# LowSide_Analog_protections.net
KiCad netlist of a schematic drawn in Altium Designer
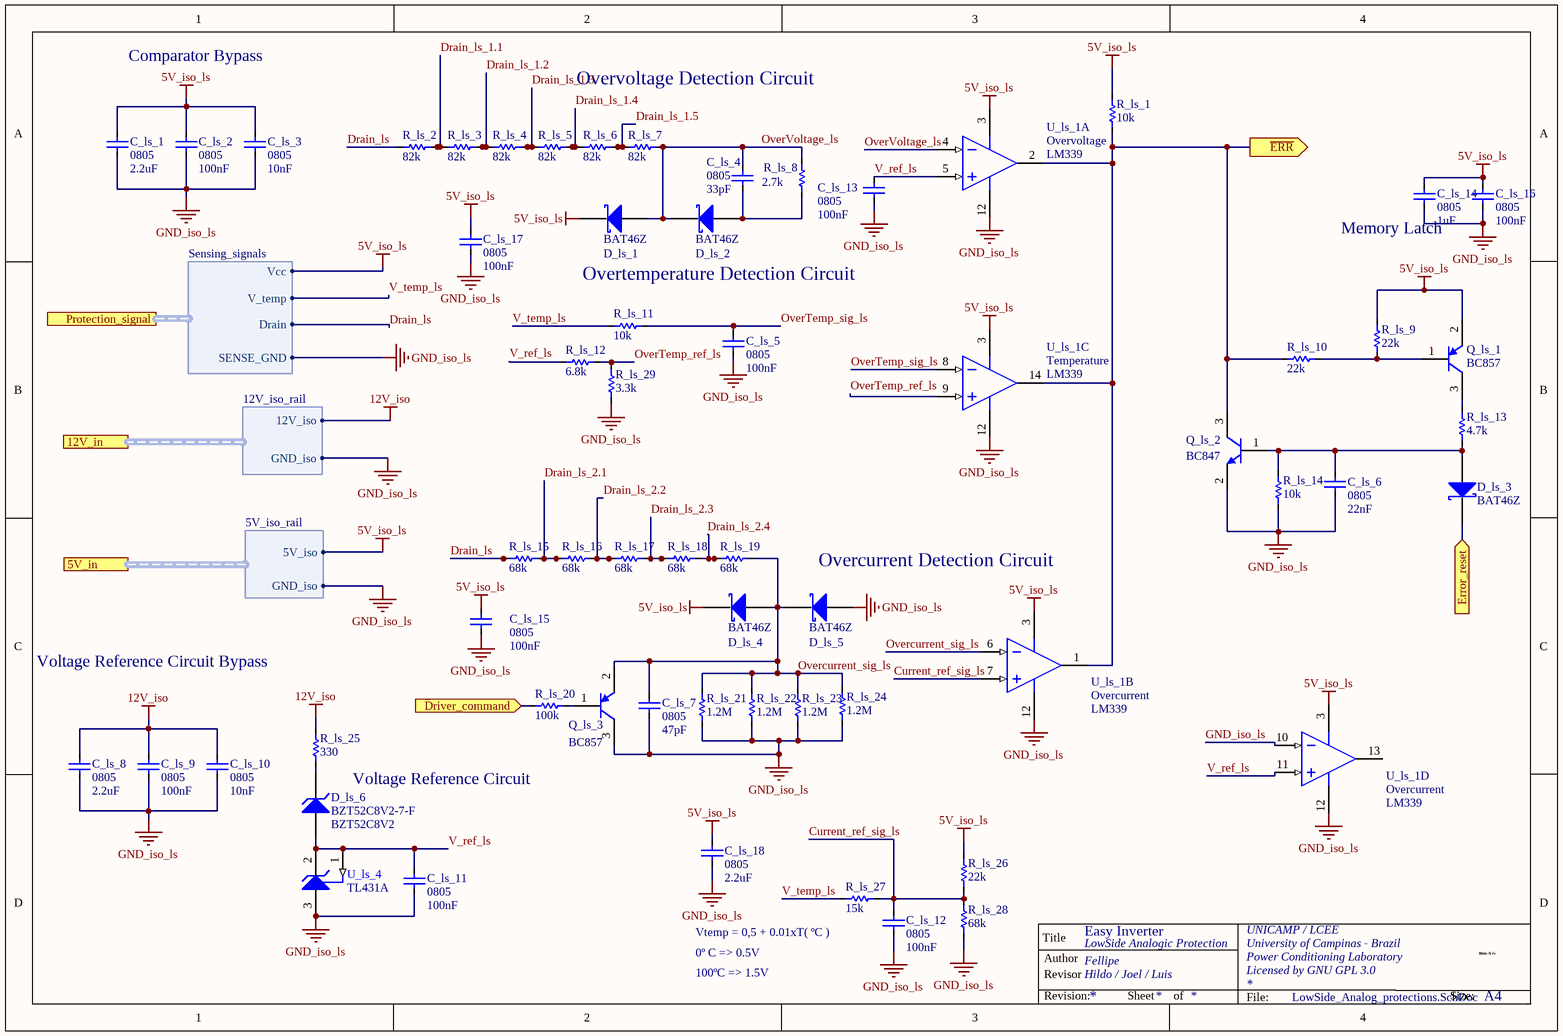
[diagram p0: LowSide_Analog_protections.SchDoc]

(export (version "E")
  (design (tool "Eeschema 10.0.6"))
  (components
    (comp (ref "C_ls_1")
      (value "0805")
      (footprint "Capacitor 0805")
      (description "SMD ceramic capacitor 0805")
      (fields (field (name "ALTIUM_VALUE") "2.2uF"))
      (libsource (lib "EdgeInverter_library") (part "Capacitor 0805"))
    )
    (comp (ref "C_ls_2")
      (value "0805")
      (footprint "Capacitor 0805")
      (description "SMD ceramic capacitor 0805")
      (fields (field (name "ALTIUM_VALUE") "100nF"))
      (libsource (lib "EdgeInverter_library") (part "Capacitor 0805"))
    )
    (comp (ref "C_ls_3")
      (value "0805")
      (footprint "Capacitor 0805")
      (description "SMD ceramic capacitor 0805")
      (fields (field (name "ALTIUM_VALUE") "10nF"))
      (libsource (lib "EdgeInverter_library") (part "Capacitor 0805"))
    )
    (comp (ref "C_ls_4")
      (value "0805")
      (footprint "Capacitor 0805")
      (description "SMD ceramic capacitor 0805")
      (fields (field (name "ALTIUM_VALUE") "33pF"))
      (libsource (lib "EdgeInverter_library") (part "Capacitor 0805"))
    )
    (comp (ref "C_ls_5")
      (value "0805")
      (footprint "Capacitor 0805")
      (description "SMD ceramic capacitor 0805")
      (fields (field (name "ALTIUM_VALUE") "100nF"))
      (libsource (lib "EdgeInverter_library") (part "Capacitor 0805"))
    )
    (comp (ref "C_ls_6")
      (value "0805")
      (footprint "Capacitor 0805")
      (description "SMD ceramic capacitor 0805")
      (fields (field (name "ALTIUM_VALUE") "22nF"))
      (libsource (lib "EdgeInverter_library") (part "Capacitor 0805"))
    )
    (comp (ref "C_ls_7")
      (value "0805")
      (footprint "Capacitor 0805")
      (description "SMD ceramic capacitor 0805")
      (fields (field (name "ALTIUM_VALUE") "47pF"))
      (libsource (lib "EdgeInverter_library") (part "Capacitor 0805"))
    )
    (comp (ref "C_ls_8")
      (value "0805")
      (footprint "Capacitor 0805")
      (description "SMD ceramic capacitor 0805")
      (fields (field (name "ALTIUM_VALUE") "2.2uF"))
      (libsource (lib "EdgeInverter_library") (part "Capacitor 0805"))
    )
    (comp (ref "C_ls_9")
      (value "0805")
      (footprint "Capacitor 0805")
      (description "SMD ceramic capacitor 0805")
      (fields (field (name "ALTIUM_VALUE") "100nF"))
      (libsource (lib "EdgeInverter_library") (part "Capacitor 0805"))
    )
    (comp (ref "C_ls_10")
      (value "0805")
      (footprint "Capacitor 0805")
      (description "SMD ceramic capacitor 0805")
      (fields (field (name "ALTIUM_VALUE") "10nF"))
      (libsource (lib "EdgeInverter_library") (part "Capacitor 0805"))
    )
    (comp (ref "C_ls_11")
      (value "0805")
      (footprint "Capacitor 0805")
      (description "SMD ceramic capacitor 0805")
      (fields (field (name "ALTIUM_VALUE") "100nF"))
      (libsource (lib "EdgeInverter_library") (part "Capacitor 0805"))
    )
    (comp (ref "C_ls_12")
      (value "0805")
      (footprint "Capacitor 0805")
      (description "SMD ceramic capacitor 0805")
      (fields (field (name "ALTIUM_VALUE") "100nF"))
      (libsource (lib "EdgeInverter_library") (part "Capacitor 0805"))
    )
    (comp (ref "C_ls_13")
      (value "0805")
      (footprint "Capacitor 0805")
      (description "SMD ceramic capacitor 0805")
      (fields (field (name "ALTIUM_VALUE") "100nF"))
      (libsource (lib "EdgeInverter_library") (part "Capacitor 0805"))
    )
    (comp (ref "C_ls_14")
      (value "0805")
      (footprint "Capacitor 0805")
      (description "SMD ceramic capacitor 0805")
      (fields (field (name "ALTIUM_VALUE") "1uF"))
      (libsource (lib "EdgeInverter_library") (part "Capacitor 0805"))
    )
    (comp (ref "C_ls_15")
      (value "0805")
      (footprint "Capacitor 0805")
      (description "SMD ceramic capacitor 0805")
      (fields (field (name "ALTIUM_VALUE") "100nF"))
      (libsource (lib "EdgeInverter_library") (part "Capacitor 0805"))
    )
    (comp (ref "C_ls_16")
      (value "0805")
      (footprint "Capacitor 0805")
      (description "SMD ceramic capacitor 0805")
      (fields (field (name "ALTIUM_VALUE") "100nF"))
      (libsource (lib "EdgeInverter_library") (part "Capacitor 0805"))
    )
    (comp (ref "C_ls_17")
      (value "0805")
      (footprint "Capacitor 0805")
      (description "SMD ceramic capacitor 0805")
      (fields (field (name "ALTIUM_VALUE") "100nF"))
      (libsource (lib "EdgeInverter_library") (part "Capacitor 0805"))
    )
    (comp (ref "C_ls_18")
      (value "0805")
      (footprint "Capacitor 0805")
      (description "SMD ceramic capacitor 0805")
      (fields (field (name "ALTIUM_VALUE") "2.2uF"))
      (libsource (lib "EdgeInverter_library") (part "Capacitor 0805"))
    )
    (comp (ref "D_ls_1")
      (value "BAT46Z")
      (footprint "SOD 123")
      (description "DIODE SCHOTTKY 100V 150MA SOD123")
      (libsource (lib "EdgeInverter_library") (part "BAT46Z"))
    )
    (comp (ref "D_ls_2")
      (value "BAT46Z")
      (footprint "SOD 123")
      (description "DIODE SCHOTTKY 100V 150MA SOD123")
      (libsource (lib "EdgeInverter_library") (part "BAT46Z"))
    )
    (comp (ref "D_ls_3")
      (value "BAT46Z")
      (footprint "SOD 123")
      (description "DIODE SCHOTTKY 100V 150MA SOD123")
      (libsource (lib "EdgeInverter_library") (part "BAT46Z"))
    )
    (comp (ref "D_ls_4")
      (value "BAT46Z")
      (footprint "SOD 123")
      (description "DIODE SCHOTTKY 100V 150MA SOD123")
      (libsource (lib "EdgeInverter_library") (part "BAT46Z"))
    )
    (comp (ref "D_ls_5")
      (value "BAT46Z")
      (footprint "SOD 123")
      (description "DIODE SCHOTTKY 100V 150MA SOD123")
      (libsource (lib "EdgeInverter_library") (part "BAT46Z"))
    )
    (comp (ref "D_ls_6")
      (value "BZT52C8V2-7-F")
      (footprint "SOD 123")
      (description "DIODE ZENER 8.2V 500MW SOD123")
      (fields (field (name "ALTIUM_VALUE") "BZT52C8V2"))
      (libsource (lib "EdgeInverter_library") (part "BZT52C8V2-7-F"))
    )
    (comp (ref "Q_ls_1")
      (value "BC857")
      (footprint "SOT 23")
      (description "General Purpose Transistor, PNP Silicon, 3-Pin SOT-23, Pb-Free, Tape and Reel")
      (libsource (lib "EdgeInverter_library") (part "BC857BLT1G"))
    )
    (comp (ref "Q_ls_2")
      (value "BC847")
      (footprint "SOT 23")
      (description "General Purpose Transistor, NPN Silicon, 3-Pin SOT-23, Pb-Free, Tape and Reel")
      (libsource (lib "EdgeInverter_library") (part "BC847BLT1G"))
    )
    (comp (ref "Q_ls_3")
      (value "BC857")
      (footprint "SOT 23")
      (description "General Purpose Transistor, PNP Silicon, 3-Pin SOT-23, Pb-Free, Tape and Reel")
      (libsource (lib "EdgeInverter_library") (part "BC857BLT1G"))
    )
    (comp (ref "R_ls_1")
      (value "10k")
      (footprint "Resistor 0805")
      (description "SMD resistor 0805")
      (fields (field (name "Comment") "Resistor 0805"))
      (libsource (lib "EdgeInverter_library") (part "Resistor 0805"))
    )
    (comp (ref "R_ls_2")
      (value "82k")
      (footprint "Resistor 0805")
      (description "SMD resistor 0805")
      (fields (field (name "Comment") "Resistor 0805"))
      (libsource (lib "EdgeInverter_library") (part "Resistor 0805"))
    )
    (comp (ref "R_ls_3")
      (value "82k")
      (footprint "Resistor 0805")
      (description "SMD resistor 0805")
      (fields (field (name "Comment") "Resistor 0805"))
      (libsource (lib "EdgeInverter_library") (part "Resistor 0805"))
    )
    (comp (ref "R_ls_4")
      (value "82k")
      (footprint "Resistor 0805")
      (description "SMD resistor 0805")
      (fields (field (name "Comment") "Resistor 0805"))
      (libsource (lib "EdgeInverter_library") (part "Resistor 0805"))
    )
    (comp (ref "R_ls_5")
      (value "82k")
      (footprint "Resistor 0805")
      (description "SMD resistor 0805")
      (fields (field (name "Comment") "Resistor 0805"))
      (libsource (lib "EdgeInverter_library") (part "Resistor 0805"))
    )
    (comp (ref "R_ls_6")
      (value "82k")
      (footprint "Resistor 0805")
      (description "SMD resistor 0805")
      (fields (field (name "Comment") "Resistor 0805"))
      (libsource (lib "EdgeInverter_library") (part "Resistor 0805"))
    )
    (comp (ref "R_ls_7")
      (value "82k")
      (footprint "Resistor 0805")
      (description "SMD resistor 0805")
      (fields (field (name "Comment") "Resistor 0805"))
      (libsource (lib "EdgeInverter_library") (part "Resistor 0805"))
    )
    (comp (ref "R_ls_8")
      (value "2.7k")
      (footprint "Resistor 0805")
      (description "SMD resistor 0805")
      (fields (field (name "Comment") "Resistor 0805"))
      (libsource (lib "EdgeInverter_library") (part "Resistor 0805"))
    )
    (comp (ref "R_ls_9")
      (value "22k")
      (footprint "Resistor 0805")
      (description "SMD resistor 0805")
      (fields (field (name "Comment") "Resistor 0805"))
      (libsource (lib "EdgeInverter_library") (part "Resistor 0805"))
    )
    (comp (ref "R_ls_10")
      (value "22k")
      (footprint "Resistor 0805")
      (description "SMD resistor 0805")
      (fields (field (name "Comment") "Resistor 0805"))
      (libsource (lib "EdgeInverter_library") (part "Resistor 0805"))
    )
    (comp (ref "R_ls_11")
      (value "10k")
      (footprint "Resistor 0805")
      (description "SMD resistor 0805")
      (fields (field (name "Comment") "Resistor 0805"))
      (libsource (lib "EdgeInverter_library") (part "Resistor 0805"))
    )
    (comp (ref "R_ls_12")
      (value "6.8k")
      (footprint "Resistor 0805")
      (description "SMD resistor 0805")
      (fields (field (name "Comment") "Resistor 0805"))
      (libsource (lib "EdgeInverter_library") (part "Resistor 0805"))
    )
    (comp (ref "R_ls_13")
      (value "4.7k")
      (footprint "Resistor 0805")
      (description "SMD resistor 0805")
      (fields (field (name "Comment") "Resistor 0805"))
      (libsource (lib "EdgeInverter_library") (part "Resistor 0805"))
    )
    (comp (ref "R_ls_14")
      (value "10k")
      (footprint "Resistor 0805")
      (description "SMD resistor 0805")
      (fields (field (name "Comment") "Resistor 0805"))
      (libsource (lib "EdgeInverter_library") (part "Resistor 0805"))
    )
    (comp (ref "R_ls_15")
      (value "68k")
      (footprint "Resistor 0805")
      (description "SMD resistor 0805")
      (fields (field (name "Comment") "Resistor 0805"))
      (libsource (lib "EdgeInverter_library") (part "Resistor 0805"))
    )
    (comp (ref "R_ls_16")
      (value "68k")
      (footprint "Resistor 0805")
      (description "SMD resistor 0805")
      (fields (field (name "Comment") "Resistor 0805"))
      (libsource (lib "EdgeInverter_library") (part "Resistor 0805"))
    )
    (comp (ref "R_ls_17")
      (value "68k")
      (footprint "Resistor 0805")
      (description "SMD resistor 0805")
      (fields (field (name "Comment") "Resistor 0805"))
      (libsource (lib "EdgeInverter_library") (part "Resistor 0805"))
    )
    (comp (ref "R_ls_18")
      (value "68k")
      (footprint "Resistor 0805")
      (description "SMD resistor 0805")
      (fields (field (name "Comment") "Resistor 0805"))
      (libsource (lib "EdgeInverter_library") (part "Resistor 0805"))
    )
    (comp (ref "R_ls_19")
      (value "68k")
      (footprint "Resistor 0805")
      (description "SMD resistor 0805")
      (fields (field (name "Comment") "Resistor 0805"))
      (libsource (lib "EdgeInverter_library") (part "Resistor 0805"))
    )
    (comp (ref "R_ls_20")
      (value "100k")
      (footprint "Resistor 0805")
      (description "SMD resistor 0805")
      (fields (field (name "Comment") "Resistor 0805"))
      (libsource (lib "EdgeInverter_library") (part "Resistor 0805"))
    )
    (comp (ref "R_ls_21")
      (value "1.2M")
      (footprint "Resistor 0805")
      (description "SMD resistor 0805")
      (fields (field (name "Comment") "Resistor 0805"))
      (libsource (lib "EdgeInverter_library") (part "Resistor 0805"))
    )
    (comp (ref "R_ls_22")
      (value "1.2M")
      (footprint "Resistor 0805")
      (description "SMD resistor 0805")
      (fields (field (name "Comment") "Resistor 0805"))
      (libsource (lib "EdgeInverter_library") (part "Resistor 0805"))
    )
    (comp (ref "R_ls_23")
      (value "1.2M")
      (footprint "Resistor 0805")
      (description "SMD resistor 0805")
      (fields (field (name "Comment") "Resistor 0805"))
      (libsource (lib "EdgeInverter_library") (part "Resistor 0805"))
    )
    (comp (ref "R_ls_24")
      (value "1.2M")
      (footprint "Resistor 0805")
      (description "SMD resistor 0805")
      (fields (field (name "Comment") "Resistor 0805"))
      (libsource (lib "EdgeInverter_library") (part "Resistor 0805"))
    )
    (comp (ref "R_ls_25")
      (value "330")
      (footprint "Resistor 0805")
      (description "SMD resistor 0805")
      (fields (field (name "Comment") "Resistor 0805"))
      (libsource (lib "EdgeInverter_library") (part "Resistor 0805"))
    )
    (comp (ref "R_ls_26")
      (value "22k")
      (footprint "Resistor 0805")
      (description "SMD resistor 0805")
      (fields (field (name "Comment") "Resistor 0805"))
      (libsource (lib "EdgeInverter_library") (part "Resistor 0805"))
    )
    (comp (ref "R_ls_27")
      (value "15k")
      (footprint "Resistor 0805")
      (description "SMD resistor 0805")
      (fields (field (name "Comment") "Resistor 0805"))
      (libsource (lib "EdgeInverter_library") (part "Resistor 0805"))
    )
    (comp (ref "R_ls_28")
      (value "68k")
      (footprint "Resistor 0805")
      (description "SMD resistor 0805")
      (fields (field (name "Comment") "Resistor 0805"))
      (libsource (lib "EdgeInverter_library") (part "Resistor 0805"))
    )
    (comp (ref "R_ls_29")
      (value "3.3k")
      (footprint "Resistor 0805")
      (description "SMD resistor 0805")
      (fields (field (name "Comment") "Resistor 0805"))
      (libsource (lib "EdgeInverter_library") (part "Resistor 0805"))
    )
    (comp (ref "U_ls_1")
      (value "Overvoltage")
      (footprint "SOIC 14")
      (description "Low Power Low Offset Voltage Quad Comparator, 14-pin Narrow SOIC")
      (fields (field (name "ALTIUM_VALUE") "LM339"))
      (libsource (lib "EdgeInverter_library") (part "LM339"))
    )
    (comp (ref "U_ls_4")
      (value "TL431A")
      (footprint "SOT 23")
      (description "IC VREF SHUNT ADJ SOT23-3")
      (libsource (lib "EdgeInverter_library") (part "TL431A"))
    )
  )
  (nets
    (net (code "4") (name "/Current_ref_sig_ls") (class "Default")
      (node (ref "C_ls_12") (pin "1") (pinfunction "1_1") (pintype "passive"))
      (node (ref "R_ls_26") (pin "1") (pinfunction "1_1") (pintype "passive"))
      (node (ref "R_ls_27") (pin "2") (pinfunction "2_2") (pintype "passive"))
      (node (ref "R_ls_28") (pin "2") (pinfunction "2_2") (pintype "passive"))
      (node (ref "U_ls_1") (pin "7") (pinfunction "IN2+_7") (pintype "input"))
    )
    (net (code "5") (name "/Drain_ls") (class "Default")
      (node (ref "R_ls_15") (pin "1") (pinfunction "1_1") (pintype "passive"))
      (node (ref "R_ls_2") (pin "1") (pinfunction "1_1") (pintype "passive"))
    )
    (net (code "6") (name "/Drain_ls_1.1") (class "Default")
      (node (ref "R_ls_2") (pin "2") (pinfunction "2_2") (pintype "passive"))
      (node (ref "R_ls_3") (pin "1") (pinfunction "1_1") (pintype "passive"))
    )
    (net (code "7") (name "/Drain_ls_1.2") (class "Default")
      (node (ref "R_ls_3") (pin "2") (pinfunction "2_2") (pintype "passive"))
      (node (ref "R_ls_4") (pin "1") (pinfunction "1_1") (pintype "passive"))
    )
    (net (code "8") (name "/Drain_ls_1.3") (class "Default")
      (node (ref "R_ls_4") (pin "2") (pinfunction "2_2") (pintype "passive"))
      (node (ref "R_ls_5") (pin "1") (pinfunction "1_1") (pintype "passive"))
    )
    (net (code "9") (name "/Drain_ls_1.4") (class "Default")
      (node (ref "R_ls_5") (pin "2") (pinfunction "2_2") (pintype "passive"))
      (node (ref "R_ls_6") (pin "1") (pinfunction "1_1") (pintype "passive"))
    )
    (net (code "10") (name "/Drain_ls_1.5") (class "Default")
      (node (ref "R_ls_6") (pin "2") (pinfunction "2_2") (pintype "passive"))
      (node (ref "R_ls_7") (pin "1") (pinfunction "1_1") (pintype "passive"))
    )
    (net (code "11") (name "/Drain_ls_2.1") (class "Default")
      (node (ref "R_ls_15") (pin "2") (pinfunction "2_2") (pintype "passive"))
      (node (ref "R_ls_16") (pin "1") (pinfunction "1_1") (pintype "passive"))
    )
    (net (code "12") (name "/Drain_ls_2.2") (class "Default")
      (node (ref "R_ls_16") (pin "2") (pinfunction "2_2") (pintype "passive"))
      (node (ref "R_ls_17") (pin "1") (pinfunction "1_1") (pintype "passive"))
    )
    (net (code "13") (name "/Drain_ls_2.3") (class "Default")
      (node (ref "R_ls_17") (pin "2") (pinfunction "2_2") (pintype "passive"))
      (node (ref "R_ls_18") (pin "1") (pinfunction "1_1") (pintype "passive"))
    )
    (net (code "14") (name "/Drain_ls_2.4") (class "Default")
      (node (ref "R_ls_18") (pin "2") (pinfunction "2_2") (pintype "passive"))
      (node (ref "R_ls_19") (pin "1") (pinfunction "1_1") (pintype "passive"))
    )
    (net (code "15") (name "/Driver_command") (class "Default")
      (node (ref "R_ls_20") (pin "2") (pinfunction "2_2") (pintype "passive"))
    )
    (net (code "16") (name "/Error_reset") (class "Default")
      (node (ref "D_ls_3") (pin "2") (pinfunction "K_2") (pintype "passive"))
    )
    (net (code "17") (name "/OverTemp_ref_ls") (class "Default")
      (node (ref "R_ls_12") (pin "2") (pinfunction "2_2") (pintype "passive"))
      (node (ref "R_ls_29") (pin "2") (pinfunction "2_2") (pintype "passive"))
      (node (ref "U_ls_1") (pin "9") (pinfunction "IN3+_9") (pintype "input"))
    )
    (net (code "18") (name "/OverTemp_sig_ls") (class "Default")
      (node (ref "C_ls_5") (pin "1") (pinfunction "1_1") (pintype "passive"))
      (node (ref "R_ls_11") (pin "2") (pinfunction "2_2") (pintype "passive"))
      (node (ref "U_ls_1") (pin "8") (pinfunction "IN3-_8") (pintype "input"))
    )
    (net (code "19") (name "/OverVoltage_ls") (class "Default")
      (node (ref "C_ls_4") (pin "1") (pinfunction "1_1") (pintype "passive"))
      (node (ref "D_ls_1") (pin "1") (pinfunction "A_1") (pintype "passive"))
      (node (ref "D_ls_2") (pin "2") (pinfunction "K_2") (pintype "passive"))
      (node (ref "R_ls_7") (pin "2") (pinfunction "2_2") (pintype "passive"))
      (node (ref "R_ls_8") (pin "2") (pinfunction "2_2") (pintype "passive"))
      (node (ref "U_ls_1") (pin "4") (pinfunction "IN1-_4") (pintype "input"))
    )
    (net (code "20") (name "/Overcurrent_sig_ls") (class "Default")
      (node (ref "C_ls_7") (pin "1") (pinfunction "1_1") (pintype "passive"))
      (node (ref "D_ls_4") (pin "1") (pinfunction "A_1") (pintype "passive"))
      (node (ref "D_ls_5") (pin "2") (pinfunction "K_2") (pintype "passive"))
      (node (ref "Q_ls_3") (pin "2") (pinfunction "E_2") (pintype "passive"))
      (node (ref "R_ls_19") (pin "2") (pinfunction "2_2") (pintype "passive"))
      (node (ref "R_ls_21") (pin "2") (pinfunction "2_2") (pintype "passive"))
      (node (ref "R_ls_22") (pin "2") (pinfunction "2_2") (pintype "passive"))
      (node (ref "R_ls_23") (pin "2") (pinfunction "2_2") (pintype "passive"))
      (node (ref "R_ls_24") (pin "2") (pinfunction "2_2") (pintype "passive"))
      (node (ref "U_ls_1") (pin "6") (pinfunction "IN2-_6") (pintype "input"))
    )
    (net (code "21") (name "/V_ref_ls") (class "Default")
      (node (ref "C_ls_11") (pin "1") (pinfunction "1_1") (pintype "passive"))
      (node (ref "C_ls_13") (pin "1") (pinfunction "1_1") (pintype "passive"))
      (node (ref "D_ls_6") (pin "1") (pinfunction "A_1") (pintype "passive"))
      (node (ref "R_ls_12") (pin "1") (pinfunction "1_1") (pintype "passive"))
      (node (ref "U_ls_1") (pin "11") (pinfunction "IN4+_11") (pintype "input"))
      (node (ref "U_ls_1") (pin "5") (pinfunction "IN1+_5") (pintype "input"))
      (node (ref "U_ls_4") (pin "1") (pinfunction "REF_1") (pintype "input"))
      (node (ref "U_ls_4") (pin "2") (pinfunction "CATHODE_2") (pintype "passive"))
    )
    (net (code "22") (name "/V_temp_ls") (class "Default")
      (node (ref "R_ls_11") (pin "1") (pinfunction "1_1") (pintype "passive"))
      (node (ref "R_ls_27") (pin "1") (pinfunction "1_1") (pintype "passive"))
    )
    (net (code "26") (name "/~{ERR}") (class "Default")
      (node (ref "Q_ls_2") (pin "3") (pinfunction "C_3") (pintype "passive"))
      (node (ref "R_ls_1") (pin "1") (pinfunction "1_1") (pintype "passive"))
      (node (ref "R_ls_10") (pin "1") (pinfunction "1_1") (pintype "passive"))
      (node (ref "U_ls_1") (pin "1") (pinfunction "OUT2_1") (pintype "open_collector"))
      (node (ref "U_ls_1") (pin "14") (pinfunction "OUT3_14") (pintype "open_collector"))
      (node (ref "U_ls_1") (pin "2") (pinfunction "OUT1_2") (pintype "open_collector"))
    )
    (net (code "27") (name "5V_iso_ls") (class "Default")
      (node (ref "C_ls_1") (pin "1") (pinfunction "1_1") (pintype "passive"))
      (node (ref "C_ls_14") (pin "1") (pinfunction "1_1") (pintype "passive"))
      (node (ref "C_ls_15") (pin "1") (pinfunction "1_1") (pintype "passive"))
      (node (ref "C_ls_16") (pin "1") (pinfunction "1_1") (pintype "passive"))
      (node (ref "C_ls_17") (pin "1") (pinfunction "1_1") (pintype "passive"))
      (node (ref "C_ls_18") (pin "1") (pinfunction "1_1") (pintype "passive"))
      (node (ref "C_ls_2") (pin "1") (pinfunction "1_1") (pintype "passive"))
      (node (ref "C_ls_3") (pin "1") (pinfunction "1_1") (pintype "passive"))
      (node (ref "D_ls_1") (pin "2") (pinfunction "K_2") (pintype "passive"))
      (node (ref "D_ls_4") (pin "2") (pinfunction "K_2") (pintype "passive"))
      (node (ref "Q_ls_1") (pin "2") (pinfunction "E_2") (pintype "passive"))
      (node (ref "R_ls_1") (pin "2") (pinfunction "2_2") (pintype "passive"))
      (node (ref "R_ls_26") (pin "2") (pinfunction "2_2") (pintype "passive"))
      (node (ref "R_ls_9") (pin "2") (pinfunction "2_2") (pintype "passive"))
      (node (ref "U_ls_1") (pin "3") (pinfunction "V+_3") (pintype "power_in"))
    )
    (net (code "28") (name "12V_iso") (class "Default")
      (node (ref "C_ls_10") (pin "1") (pinfunction "1_1") (pintype "passive"))
      (node (ref "C_ls_8") (pin "1") (pinfunction "1_1") (pintype "passive"))
      (node (ref "C_ls_9") (pin "1") (pinfunction "1_1") (pintype "passive"))
      (node (ref "R_ls_25") (pin "2") (pinfunction "2_2") (pintype "passive"))
    )
    (net (code "29") (name "GND_iso_ls") (class "Default")
      (node (ref "C_ls_1") (pin "2") (pinfunction "2_2") (pintype "passive"))
      (node (ref "C_ls_10") (pin "2") (pinfunction "2_2") (pintype "passive"))
      (node (ref "C_ls_11") (pin "2") (pinfunction "2_2") (pintype "passive"))
      (node (ref "C_ls_12") (pin "2") (pinfunction "2_2") (pintype "passive"))
      (node (ref "C_ls_13") (pin "2") (pinfunction "2_2") (pintype "passive"))
      (node (ref "C_ls_14") (pin "2") (pinfunction "2_2") (pintype "passive"))
      (node (ref "C_ls_15") (pin "2") (pinfunction "2_2") (pintype "passive"))
      (node (ref "C_ls_16") (pin "2") (pinfunction "2_2") (pintype "passive"))
      (node (ref "C_ls_17") (pin "2") (pinfunction "2_2") (pintype "passive"))
      (node (ref "C_ls_18") (pin "2") (pinfunction "2_2") (pintype "passive"))
      (node (ref "C_ls_2") (pin "2") (pinfunction "2_2") (pintype "passive"))
      (node (ref "C_ls_3") (pin "2") (pinfunction "2_2") (pintype "passive"))
      (node (ref "C_ls_5") (pin "2") (pinfunction "2_2") (pintype "passive"))
      (node (ref "C_ls_6") (pin "2") (pinfunction "2_2") (pintype "passive"))
      (node (ref "C_ls_7") (pin "2") (pinfunction "2_2") (pintype "passive"))
      (node (ref "C_ls_8") (pin "2") (pinfunction "2_2") (pintype "passive"))
      (node (ref "C_ls_9") (pin "2") (pinfunction "2_2") (pintype "passive"))
      (node (ref "D_ls_5") (pin "1") (pinfunction "A_1") (pintype "passive"))
      (node (ref "Q_ls_2") (pin "2") (pinfunction "E_2") (pintype "passive"))
      (node (ref "Q_ls_3") (pin "3") (pinfunction "C_3") (pintype "passive"))
      (node (ref "R_ls_14") (pin "1") (pinfunction "1_1") (pintype "passive"))
      (node (ref "R_ls_21") (pin "1") (pinfunction "1_1") (pintype "passive"))
      (node (ref "R_ls_22") (pin "1") (pinfunction "1_1") (pintype "passive"))
      (node (ref "R_ls_23") (pin "1") (pinfunction "1_1") (pintype "passive"))
      (node (ref "R_ls_24") (pin "1") (pinfunction "1_1") (pintype "passive"))
      (node (ref "R_ls_28") (pin "1") (pinfunction "1_1") (pintype "passive"))
      (node (ref "R_ls_29") (pin "1") (pinfunction "1_1") (pintype "passive"))
      (node (ref "U_ls_1") (pin "10") (pinfunction "IN4-_10") (pintype "input"))
      (node (ref "U_ls_1") (pin "12") (pinfunction "GND_12") (pintype "power_in"))
      (node (ref "U_ls_4") (pin "3") (pinfunction "ANODE_3") (pintype "passive"))
    )
    (net (code "30") (name "Net-(D_ls_2-A)") (class "Default")
      (node (ref "C_ls_4") (pin "2") (pinfunction "2_2") (pintype "passive"))
      (node (ref "D_ls_2") (pin "1") (pinfunction "A_1") (pintype "passive"))
      (node (ref "R_ls_8") (pin "1") (pinfunction "1_1") (pintype "passive"))
    )
    (net (code "31") (name "Net-(D_ls_3-A)") (class "Default")
      (node (ref "C_ls_6") (pin "1") (pinfunction "1_1") (pintype "passive"))
      (node (ref "D_ls_3") (pin "1") (pinfunction "A_1") (pintype "passive"))
      (node (ref "Q_ls_2") (pin "1") (pinfunction "B_1") (pintype "passive"))
      (node (ref "R_ls_13") (pin "1") (pinfunction "1_1") (pintype "passive"))
      (node (ref "R_ls_14") (pin "2") (pinfunction "2_2") (pintype "passive"))
    )
    (net (code "32") (name "Net-(D_ls_6-K)") (class "Default")
      (node (ref "D_ls_6") (pin "2") (pinfunction "K_2") (pintype "passive"))
      (node (ref "R_ls_25") (pin "1") (pinfunction "1_1") (pintype "passive"))
    )
    (net (code "33") (name "Net-(Q_ls_1-B)") (class "Default")
      (node (ref "Q_ls_1") (pin "1") (pinfunction "B_1") (pintype "passive"))
      (node (ref "R_ls_10") (pin "2") (pinfunction "2_2") (pintype "passive"))
      (node (ref "R_ls_9") (pin "1") (pinfunction "1_1") (pintype "passive"))
    )
    (net (code "34") (name "Net-(Q_ls_1-C)") (class "Default")
      (node (ref "Q_ls_1") (pin "3") (pinfunction "C_3") (pintype "passive"))
      (node (ref "R_ls_13") (pin "2") (pinfunction "2_2") (pintype "passive"))
    )
    (net (code "35") (name "Net-(Q_ls_3-B)") (class "Default")
      (node (ref "Q_ls_3") (pin "1") (pinfunction "B_1") (pintype "passive"))
      (node (ref "R_ls_20") (pin "1") (pinfunction "1_1") (pintype "passive"))
    )
    (net (code "36") (name "unconnected-(U_ls_1D-OUT4-Pad13)") (class "Default")
      (node (ref "U_ls_1") (pin "13") (pinfunction "OUT4_13") (pintype "open_collector"))
    )
  )
)
